# FPGA_MISC.net
KiCad netlist of a schematic drawn in Altium Designer
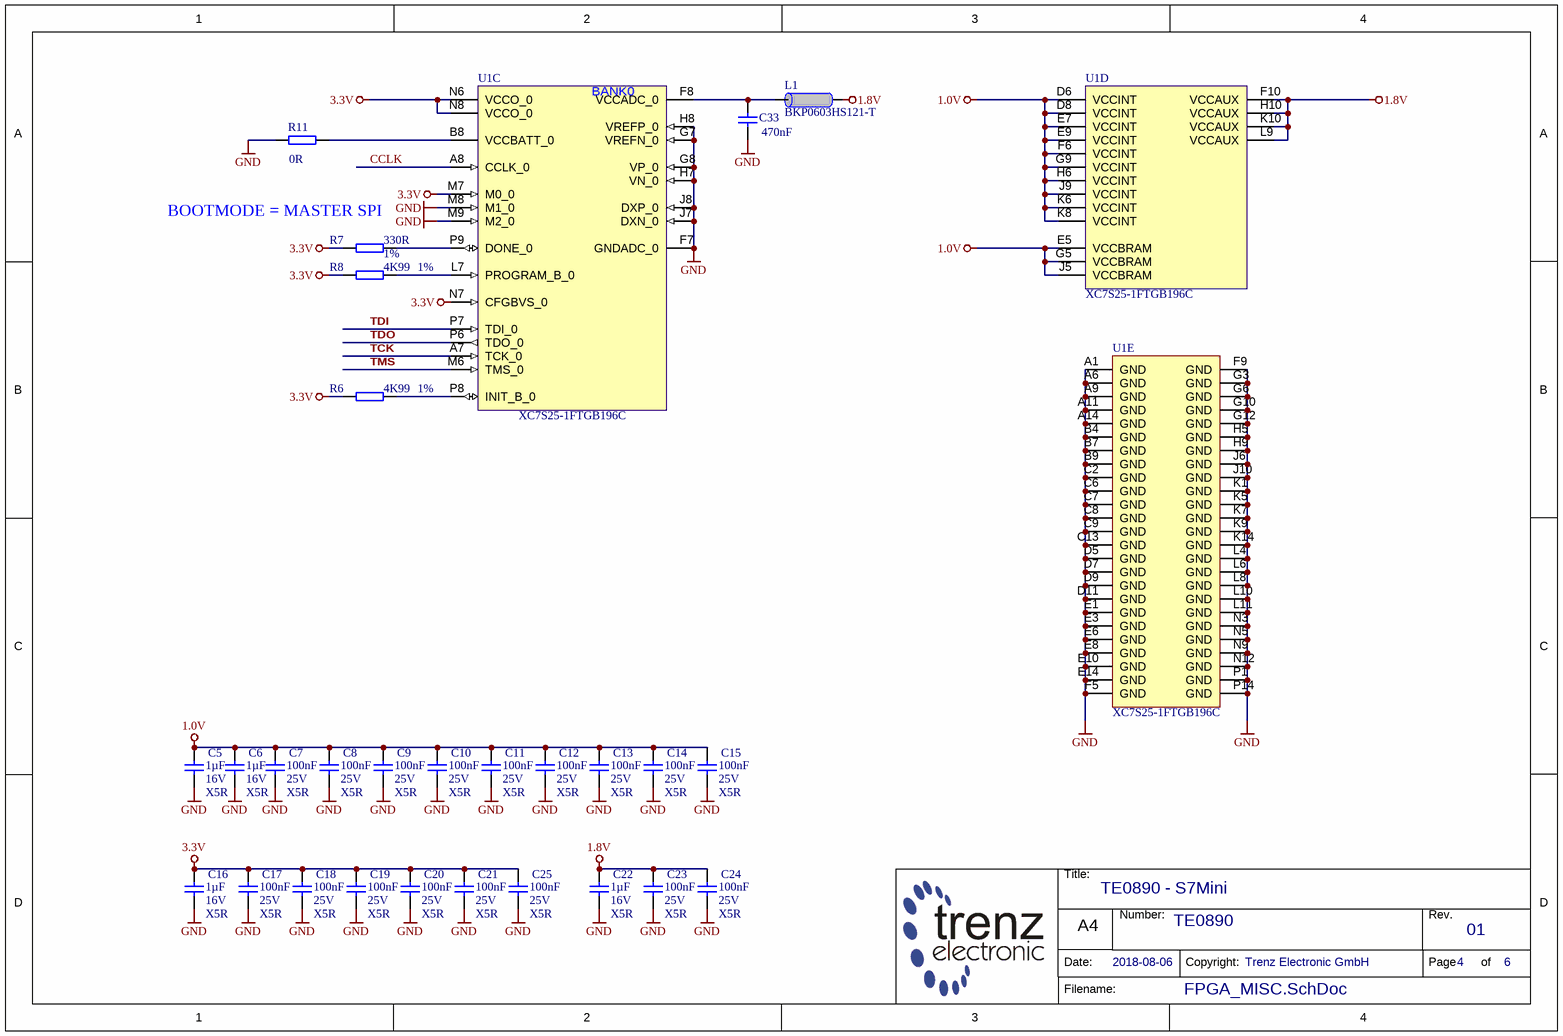
[diagram p0: FPGA_MISC.SchDoc]

(export (version "E")
  (design (tool "Eeschema 10.0.6"))
  (components
    (comp (ref "C5")
      (value "1µF")
      (footprint "CAPC1005X55N")
      (description "KON 1µF 16V X5R 10% SMD BF 1005 (0402)")
      (fields
        (field (name "VOLTAGE") "16V")
        (field (name "TECHNOLOGY") "X5R")
        (field (name "TOLERANCE") "10%")
      )
      (libsource (lib "TE") (part "CAP-NP"))
    )
    (comp (ref "C6")
      (value "1µF")
      (footprint "CAPC1005X55N")
      (description "KON 1µF 16V X5R 10% SMD BF 1005 (0402)")
      (fields
        (field (name "VOLTAGE") "16V")
        (field (name "TECHNOLOGY") "X5R")
        (field (name "TOLERANCE") "10%")
      )
      (libsource (lib "TE") (part "CAP-NP"))
    )
    (comp (ref "C7")
      (value "100nF")
      (footprint "CAPC1005X55N")
      (description "KON 100nF 25V X5R ±10% SMD BF 1005 (0402)")
      (fields (field (name "VOLTAGE") "25V") (field (name "TECHNOLOGY") "X5R"))
      (libsource (lib "TE") (part "CAP-NP"))
    )
    (comp (ref "C8")
      (value "100nF")
      (footprint "CAPC1005X55N")
      (description "KON 100nF 25V X5R ±10% SMD BF 1005 (0402)")
      (fields (field (name "VOLTAGE") "25V") (field (name "TECHNOLOGY") "X5R"))
      (libsource (lib "TE") (part "CAP-NP"))
    )
    (comp (ref "C9")
      (value "100nF")
      (footprint "CAPC1005X55N")
      (description "KON 100nF 25V X5R ±10% SMD BF 1005 (0402)")
      (fields (field (name "VOLTAGE") "25V") (field (name "TECHNOLOGY") "X5R"))
      (libsource (lib "TE") (part "CAP-NP"))
    )
    (comp (ref "C10")
      (value "100nF")
      (footprint "CAPC1005X55N")
      (description "KON 100nF 25V X5R ±10% SMD BF 1005 (0402)")
      (fields (field (name "VOLTAGE") "25V") (field (name "TECHNOLOGY") "X5R"))
      (libsource (lib "TE") (part "CAP-NP"))
    )
    (comp (ref "C11")
      (value "100nF")
      (footprint "CAPC1005X55N")
      (description "KON 100nF 25V X5R ±10% SMD BF 1005 (0402)")
      (fields (field (name "VOLTAGE") "25V") (field (name "TECHNOLOGY") "X5R"))
      (libsource (lib "TE") (part "CAP-NP"))
    )
    (comp (ref "C12")
      (value "100nF")
      (footprint "CAPC1005X55N")
      (description "KON 100nF 25V X5R ±10% SMD BF 1005 (0402)")
      (fields (field (name "VOLTAGE") "25V") (field (name "TECHNOLOGY") "X5R"))
      (libsource (lib "TE") (part "CAP-NP"))
    )
    (comp (ref "C13")
      (value "100nF")
      (footprint "CAPC1005X55N")
      (description "KON 100nF 25V X5R ±10% SMD BF 1005 (0402)")
      (fields (field (name "VOLTAGE") "25V") (field (name "TECHNOLOGY") "X5R"))
      (libsource (lib "TE") (part "CAP-NP"))
    )
    (comp (ref "C14")
      (value "100nF")
      (footprint "CAPC1005X55N")
      (description "KON 100nF 25V X5R ±10% SMD BF 1005 (0402)")
      (fields (field (name "VOLTAGE") "25V") (field (name "TECHNOLOGY") "X5R"))
      (libsource (lib "TE") (part "CAP-NP"))
    )
    (comp (ref "C15")
      (value "100nF")
      (footprint "CAPC1005X55N")
      (description "KON 100nF 25V X5R ±10% SMD BF 1005 (0402)")
      (fields (field (name "VOLTAGE") "25V") (field (name "TECHNOLOGY") "X5R"))
      (libsource (lib "TE") (part "CAP-NP"))
    )
    (comp (ref "C16")
      (value "1µF")
      (footprint "CAPC1005X55N")
      (description "KON 1µF 16V X5R 10% SMD BF 1005 (0402)")
      (fields
        (field (name "VOLTAGE") "16V")
        (field (name "TECHNOLOGY") "X5R")
        (field (name "TOLERANCE") "10%")
      )
      (libsource (lib "TE") (part "CAP-NP"))
    )
    (comp (ref "C17")
      (value "100nF")
      (footprint "CAPC1005X55N")
      (description "KON 100nF 25V X5R ±10% SMD BF 1005 (0402)")
      (fields (field (name "VOLTAGE") "25V") (field (name "TECHNOLOGY") "X5R"))
      (libsource (lib "TE") (part "CAP-NP"))
    )
    (comp (ref "C18")
      (value "100nF")
      (footprint "CAPC1005X55N")
      (description "KON 100nF 25V X5R ±10% SMD BF 1005 (0402)")
      (fields (field (name "VOLTAGE") "25V") (field (name "TECHNOLOGY") "X5R"))
      (libsource (lib "TE") (part "CAP-NP"))
    )
    (comp (ref "C19")
      (value "100nF")
      (footprint "CAPC1005X55N")
      (description "KON 100nF 25V X5R ±10% SMD BF 1005 (0402)")
      (fields (field (name "VOLTAGE") "25V") (field (name "TECHNOLOGY") "X5R"))
      (libsource (lib "TE") (part "CAP-NP"))
    )
    (comp (ref "C20")
      (value "100nF")
      (footprint "CAPC1005X55N")
      (description "KON 100nF 25V X5R ±10% SMD BF 1005 (0402)")
      (fields (field (name "VOLTAGE") "25V") (field (name "TECHNOLOGY") "X5R"))
      (libsource (lib "TE") (part "CAP-NP"))
    )
    (comp (ref "C21")
      (value "100nF")
      (footprint "CAPC1005X55N")
      (description "KON 100nF 25V X5R ±10% SMD BF 1005 (0402)")
      (fields (field (name "VOLTAGE") "25V") (field (name "TECHNOLOGY") "X5R"))
      (libsource (lib "TE") (part "CAP-NP"))
    )
    (comp (ref "C22")
      (value "1µF")
      (footprint "CAPC1005X55N")
      (description "KON 1µF 16V X5R 10% SMD BF 1005 (0402)")
      (fields
        (field (name "VOLTAGE") "16V")
        (field (name "TECHNOLOGY") "X5R")
        (field (name "TOLERANCE") "10%")
      )
      (libsource (lib "TE") (part "CAP-NP"))
    )
    (comp (ref "C23")
      (value "100nF")
      (footprint "CAPC1005X55N")
      (description "KON 100nF 25V X5R ±10% SMD BF 1005 (0402)")
      (fields (field (name "VOLTAGE") "25V") (field (name "TECHNOLOGY") "X5R"))
      (libsource (lib "TE") (part "CAP-NP"))
    )
    (comp (ref "C24")
      (value "100nF")
      (footprint "CAPC1005X55N")
      (description "KON 100nF 25V X5R ±10% SMD BF 1005 (0402)")
      (fields (field (name "VOLTAGE") "25V") (field (name "TECHNOLOGY") "X5R"))
      (libsource (lib "TE") (part "CAP-NP"))
    )
    (comp (ref "C25")
      (value "100nF")
      (footprint "CAPC1005X55N")
      (description "KON 100nF 25V X5R ±10% SMD BF 1005 (0402)")
      (fields (field (name "VOLTAGE") "25V") (field (name "TECHNOLOGY") "X5R"))
      (libsource (lib "TE") (part "CAP-NP"))
    )
    (comp (ref "C33")
      (value "470nF")
      (footprint "CAPC0603X33N")
      (description "KON 470nF 6.3V X5R 20%  SMD BF 0603 (0201)")
      (fields (field (name "VOLTAGE") "6.3V") (field (name "TOLERANCE") "20%"))
      (libsource (lib "TE") (part "CAP-NP"))
    )
    (comp (ref "L1")
      (value "BKP0603HS121-T")
      (footprint "INDC0603X33N")
      (description "Ferritdurchführung SMD 0201, BKP0603HS121-T")
      (fields (field (name "TOLERANCE") "25%"))
      (libsource (lib "TE") (part "Ferritperle"))
    )
    (comp (ref "R6")
      (value "4K99")
      (footprint "RESC1005X40N")
      (description "WID SMD 4K99 1% 0,063W")
      (fields (field (name "TOLERANCE") "1%"))
      (libsource (lib "TE") (part "RES"))
    )
    (comp (ref "R7")
      (value "330R")
      (footprint "RESC1005X40N")
      (description "WID SMD 330R 1% 0,063W  BF 1005 (0402)")
      (fields (field (name "TOLERANCE") "1%"))
      (libsource (lib "TE") (part "RES"))
    )
    (comp (ref "R8")
      (value "4K99")
      (footprint "RESC1005X40N")
      (description "WID SMD 4K99 1% 0,063W")
      (fields (field (name "TOLERANCE") "1%"))
      (libsource (lib "TE") (part "RES"))
    )
    (comp (ref "R11")
      (value "0R")
      (footprint "RESC1005X40N")
      (description "WID SMD 0R")
      (fields (field (name "TOLERANCE") "1%"))
      (libsource (lib "TE") (part "RES"))
    )
    (comp (ref "U1")
      (value "XC7S25-1FTGB196C")
      (footprint "BGA196C100P14X14_1500X1500X155B50N")
      (libsource (lib "TE") (part "XC7S25-1FTGB196"))
    )
  )
  (nets
    (net (code "1") (name "/CCLK") (class "Default")
      (node (ref "U1") (pin "A8") (pinfunction "CCLK_0_A8") (pintype "input"))
    )
    (net (code "2") (name "/TCK") (class "Default")
      (node (ref "U1") (pin "A7") (pinfunction "TCK_0_A7") (pintype "input"))
    )
    (net (code "3") (name "/TDI") (class "Default")
      (node (ref "U1") (pin "P7") (pinfunction "TDI_0_P7") (pintype "input"))
    )
    (net (code "4") (name "/TDO") (class "Default")
      (node (ref "U1") (pin "P6") (pinfunction "TDO_0_P6") (pintype "output"))
    )
    (net (code "5") (name "/TMS") (class "Default")
      (node (ref "U1") (pin "M6") (pinfunction "TMS_0_M6") (pintype "input"))
    )
    (net (code "6") (name "1.0V") (class "Default")
      (node (ref "C10") (pin "1") (pinfunction "1_1") (pintype "passive"))
      (node (ref "C11") (pin "1") (pinfunction "1_1") (pintype "passive"))
      (node (ref "C12") (pin "1") (pinfunction "1_1") (pintype "passive"))
      (node (ref "C13") (pin "1") (pinfunction "1_1") (pintype "passive"))
      (node (ref "C14") (pin "1") (pinfunction "1_1") (pintype "passive"))
      (node (ref "C15") (pin "1") (pinfunction "1_1") (pintype "passive"))
      (node (ref "C5") (pin "1") (pinfunction "1_1") (pintype "passive"))
      (node (ref "C6") (pin "1") (pinfunction "1_1") (pintype "passive"))
      (node (ref "C7") (pin "1") (pinfunction "1_1") (pintype "passive"))
      (node (ref "C8") (pin "1") (pinfunction "1_1") (pintype "passive"))
      (node (ref "C9") (pin "1") (pinfunction "1_1") (pintype "passive"))
      (node (ref "U1") (pin "D6") (pinfunction "VCCINT_D6") (pintype "power_in"))
      (node (ref "U1") (pin "D8") (pinfunction "VCCINT_D8") (pintype "power_in"))
      (node (ref "U1") (pin "E5") (pinfunction "VCCBRAM_E5") (pintype "power_in"))
      (node (ref "U1") (pin "E7") (pinfunction "VCCINT_E7") (pintype "power_in"))
      (node (ref "U1") (pin "E9") (pinfunction "VCCINT_E9") (pintype "power_in"))
      (node (ref "U1") (pin "F6") (pinfunction "VCCINT_F6") (pintype "power_in"))
      (node (ref "U1") (pin "G5") (pinfunction "VCCBRAM_G5") (pintype "power_in"))
      (node (ref "U1") (pin "G9") (pinfunction "VCCINT_G9") (pintype "power_in"))
      (node (ref "U1") (pin "H6") (pinfunction "VCCINT_H6") (pintype "power_in"))
      (node (ref "U1") (pin "J5") (pinfunction "VCCBRAM_J5") (pintype "power_in"))
      (node (ref "U1") (pin "J9") (pinfunction "VCCINT_J9") (pintype "power_in"))
      (node (ref "U1") (pin "K6") (pinfunction "VCCINT_K6") (pintype "power_in"))
      (node (ref "U1") (pin "K8") (pinfunction "VCCINT_K8") (pintype "power_in"))
    )
    (net (code "7") (name "1.8V") (class "Default")
      (node (ref "C22") (pin "1") (pinfunction "1_1") (pintype "passive"))
      (node (ref "C23") (pin "1") (pinfunction "1_1") (pintype "passive"))
      (node (ref "C24") (pin "1") (pinfunction "1_1") (pintype "passive"))
      (node (ref "L1") (pin "1") (pinfunction "1_1") (pintype "passive"))
      (node (ref "U1") (pin "F10") (pinfunction "VCCAUX_F10") (pintype "power_in"))
      (node (ref "U1") (pin "H10") (pinfunction "VCCAUX_H10") (pintype "power_in"))
      (node (ref "U1") (pin "K10") (pinfunction "VCCAUX_K10") (pintype "power_in"))
      (node (ref "U1") (pin "L9") (pinfunction "VCCAUX_L9") (pintype "power_in"))
    )
    (net (code "8") (name "3.3V") (class "Default")
      (node (ref "C16") (pin "1") (pinfunction "1_1") (pintype "passive"))
      (node (ref "C17") (pin "1") (pinfunction "1_1") (pintype "passive"))
      (node (ref "C18") (pin "1") (pinfunction "1_1") (pintype "passive"))
      (node (ref "C19") (pin "1") (pinfunction "1_1") (pintype "passive"))
      (node (ref "C20") (pin "1") (pinfunction "1_1") (pintype "passive"))
      (node (ref "C21") (pin "1") (pinfunction "1_1") (pintype "passive"))
      (node (ref "C25") (pin "1") (pinfunction "1_1") (pintype "passive"))
      (node (ref "R6") (pin "1") (pinfunction "1_1") (pintype "passive"))
      (node (ref "R7") (pin "1") (pinfunction "1_1") (pintype "passive"))
      (node (ref "R8") (pin "1") (pinfunction "1_1") (pintype "passive"))
      (node (ref "U1") (pin "M7") (pinfunction "M0_0_M7") (pintype "input"))
      (node (ref "U1") (pin "N6") (pinfunction "VCCO_0_N6") (pintype "power_in"))
      (node (ref "U1") (pin "N7") (pinfunction "CFGBVS_0_N7") (pintype "input"))
      (node (ref "U1") (pin "N8") (pinfunction "VCCO_0_N8") (pintype "power_in"))
    )
    (net (code "9") (name "GND") (class "Default")
      (node (ref "C10") (pin "2") (pinfunction "2_2") (pintype "passive"))
      (node (ref "C11") (pin "2") (pinfunction "2_2") (pintype "passive"))
      (node (ref "C12") (pin "2") (pinfunction "2_2") (pintype "passive"))
      (node (ref "C13") (pin "2") (pinfunction "2_2") (pintype "passive"))
      (node (ref "C14") (pin "2") (pinfunction "2_2") (pintype "passive"))
      (node (ref "C15") (pin "2") (pinfunction "2_2") (pintype "passive"))
      (node (ref "C16") (pin "2") (pinfunction "2_2") (pintype "passive"))
      (node (ref "C17") (pin "2") (pinfunction "2_2") (pintype "passive"))
      (node (ref "C18") (pin "2") (pinfunction "2_2") (pintype "passive"))
      (node (ref "C19") (pin "2") (pinfunction "2_2") (pintype "passive"))
      (node (ref "C20") (pin "2") (pinfunction "2_2") (pintype "passive"))
      (node (ref "C21") (pin "2") (pinfunction "2_2") (pintype "passive"))
      (node (ref "C22") (pin "2") (pinfunction "2_2") (pintype "passive"))
      (node (ref "C23") (pin "2") (pinfunction "2_2") (pintype "passive"))
      (node (ref "C24") (pin "2") (pinfunction "2_2") (pintype "passive"))
      (node (ref "C25") (pin "2") (pinfunction "2_2") (pintype "passive"))
      (node (ref "C33") (pin "2") (pinfunction "2_2") (pintype "passive"))
      (node (ref "C5") (pin "2") (pinfunction "2_2") (pintype "passive"))
      (node (ref "C6") (pin "2") (pinfunction "2_2") (pintype "passive"))
      (node (ref "C7") (pin "2") (pinfunction "2_2") (pintype "passive"))
      (node (ref "C8") (pin "2") (pinfunction "2_2") (pintype "passive"))
      (node (ref "C9") (pin "2") (pinfunction "2_2") (pintype "passive"))
      (node (ref "R11") (pin "1") (pinfunction "1_1") (pintype "passive"))
      (node (ref "U1") (pin "A1") (pinfunction "GND_A1") (pintype "power_in"))
      (node (ref "U1") (pin "A11") (pinfunction "GND_A11") (pintype "power_in"))
      (node (ref "U1") (pin "A14") (pinfunction "GND_A14") (pintype "power_in"))
      (node (ref "U1") (pin "A6") (pinfunction "GND_A6") (pintype "power_in"))
      (node (ref "U1") (pin "A9") (pinfunction "GND_A9") (pintype "power_in"))
      (node (ref "U1") (pin "B4") (pinfunction "GND_B4") (pintype "power_in"))
      (node (ref "U1") (pin "B7") (pinfunction "GND_B7") (pintype "power_in"))
      (node (ref "U1") (pin "B9") (pinfunction "GND_B9") (pintype "power_in"))
      (node (ref "U1") (pin "C13") (pinfunction "GND_C13") (pintype "power_in"))
      (node (ref "U1") (pin "C2") (pinfunction "GND_C2") (pintype "power_in"))
      (node (ref "U1") (pin "C6") (pinfunction "GND_C6") (pintype "power_in"))
      (node (ref "U1") (pin "C7") (pinfunction "GND_C7") (pintype "power_in"))
      (node (ref "U1") (pin "C8") (pinfunction "GND_C8") (pintype "power_in"))
      (node (ref "U1") (pin "C9") (pinfunction "GND_C9") (pintype "power_in"))
      (node (ref "U1") (pin "D11") (pinfunction "GND_D11") (pintype "power_in"))
      (node (ref "U1") (pin "D5") (pinfunction "GND_D5") (pintype "power_in"))
      (node (ref "U1") (pin "D7") (pinfunction "GND_D7") (pintype "power_in"))
      (node (ref "U1") (pin "D9") (pinfunction "GND_D9") (pintype "power_in"))
      (node (ref "U1") (pin "E1") (pinfunction "GND_E1") (pintype "power_in"))
      (node (ref "U1") (pin "E10") (pinfunction "GND_E10") (pintype "power_in"))
      (node (ref "U1") (pin "E14") (pinfunction "GND_E14") (pintype "power_in"))
      (node (ref "U1") (pin "E3") (pinfunction "GND_E3") (pintype "power_in"))
      (node (ref "U1") (pin "E6") (pinfunction "GND_E6") (pintype "power_in"))
      (node (ref "U1") (pin "E8") (pinfunction "GND_E8") (pintype "power_in"))
      (node (ref "U1") (pin "F5") (pinfunction "GND_F5") (pintype "power_in"))
      (node (ref "U1") (pin "F7") (pinfunction "GNDADC_0_F7") (pintype "power_in"))
      (node (ref "U1") (pin "F9") (pinfunction "GND_F9") (pintype "power_in"))
      (node (ref "U1") (pin "G10") (pinfunction "GND_G10") (pintype "power_in"))
      (node (ref "U1") (pin "G12") (pinfunction "GND_G12") (pintype "power_in"))
      (node (ref "U1") (pin "G3") (pinfunction "GND_G3") (pintype "power_in"))
      (node (ref "U1") (pin "G6") (pinfunction "GND_G6") (pintype "power_in"))
      (node (ref "U1") (pin "G7") (pinfunction "VREFN_0_G7") (pintype "input"))
      (node (ref "U1") (pin "G8") (pinfunction "VP_0_G8") (pintype "input"))
      (node (ref "U1") (pin "H5") (pinfunction "GND_H5") (pintype "power_in"))
      (node (ref "U1") (pin "H7") (pinfunction "VN_0_H7") (pintype "input"))
      (node (ref "U1") (pin "H8") (pinfunction "VREFP_0_H8") (pintype "input"))
      (node (ref "U1") (pin "H9") (pinfunction "GND_H9") (pintype "power_in"))
      (node (ref "U1") (pin "J10") (pinfunction "GND_J10") (pintype "power_in"))
      (node (ref "U1") (pin "J6") (pinfunction "GND_J6") (pintype "power_in"))
      (node (ref "U1") (pin "J7") (pinfunction "DXN_0_J7") (pintype "input"))
      (node (ref "U1") (pin "J8") (pinfunction "DXP_0_J8") (pintype "input"))
      (node (ref "U1") (pin "K1") (pinfunction "GND_K1") (pintype "power_in"))
      (node (ref "U1") (pin "K14") (pinfunction "GND_K14") (pintype "power_in"))
      (node (ref "U1") (pin "K5") (pinfunction "GND_K5") (pintype "power_in"))
      (node (ref "U1") (pin "K7") (pinfunction "GND_K7") (pintype "power_in"))
      (node (ref "U1") (pin "K9") (pinfunction "GND_K9") (pintype "power_in"))
      (node (ref "U1") (pin "L10") (pinfunction "GND_L10") (pintype "power_in"))
      (node (ref "U1") (pin "L11") (pinfunction "GND_L11") (pintype "power_in"))
      (node (ref "U1") (pin "L4") (pinfunction "GND_L4") (pintype "power_in"))
      (node (ref "U1") (pin "L6") (pinfunction "GND_L6") (pintype "power_in"))
      (node (ref "U1") (pin "L8") (pinfunction "GND_L8") (pintype "power_in"))
      (node (ref "U1") (pin "M8") (pinfunction "M1_0_M8") (pintype "input"))
      (node (ref "U1") (pin "M9") (pinfunction "M2_0_M9") (pintype "input"))
      (node (ref "U1") (pin "N12") (pinfunction "GND_N12") (pintype "power_in"))
      (node (ref "U1") (pin "N3") (pinfunction "GND_N3") (pintype "power_in"))
      (node (ref "U1") (pin "N5") (pinfunction "GND_N5") (pintype "power_in"))
      (node (ref "U1") (pin "N9") (pinfunction "GND_N9") (pintype "power_in"))
      (node (ref "U1") (pin "P1") (pinfunction "GND_P1") (pintype "power_in"))
      (node (ref "U1") (pin "P14") (pinfunction "GND_P14") (pintype "power_in"))
    )
    (net (code "10") (name "Net-(U1C-DONE_0)") (class "Default")
      (node (ref "R7") (pin "2") (pinfunction "2_2") (pintype "passive"))
      (node (ref "U1") (pin "P9") (pinfunction "DONE_0_P9") (pintype "bidirectional"))
    )
    (net (code "11") (name "Net-(U1C-INIT_B_0)") (class "Default")
      (node (ref "R6") (pin "2") (pinfunction "2_2") (pintype "passive"))
      (node (ref "U1") (pin "P8") (pinfunction "INIT_B_0_P8") (pintype "bidirectional"))
    )
    (net (code "12") (name "Net-(U1C-PROGRAM_B_0)") (class "Default")
      (node (ref "R8") (pin "2") (pinfunction "2_2") (pintype "passive"))
      (node (ref "U1") (pin "L7") (pinfunction "PROGRAM_B_0_L7") (pintype "input"))
    )
    (net (code "13") (name "Net-(U1C-VCCADC_0)") (class "Default")
      (node (ref "C33") (pin "1") (pinfunction "1_1") (pintype "passive"))
      (node (ref "L1") (pin "2") (pinfunction "2_2") (pintype "passive"))
      (node (ref "U1") (pin "F8") (pinfunction "VCCADC_0_F8") (pintype "power_in"))
    )
    (net (code "14") (name "Net-(U1C-VCCBATT_0)") (class "Default")
      (node (ref "R11") (pin "2") (pinfunction "2_2") (pintype "passive"))
      (node (ref "U1") (pin "B8") (pinfunction "VCCBATT_0_B8") (pintype "power_in"))
    )
  )
)
